# mbed_programmer_1.net
KiCad netlist of a schematic drawn in Altium Designer
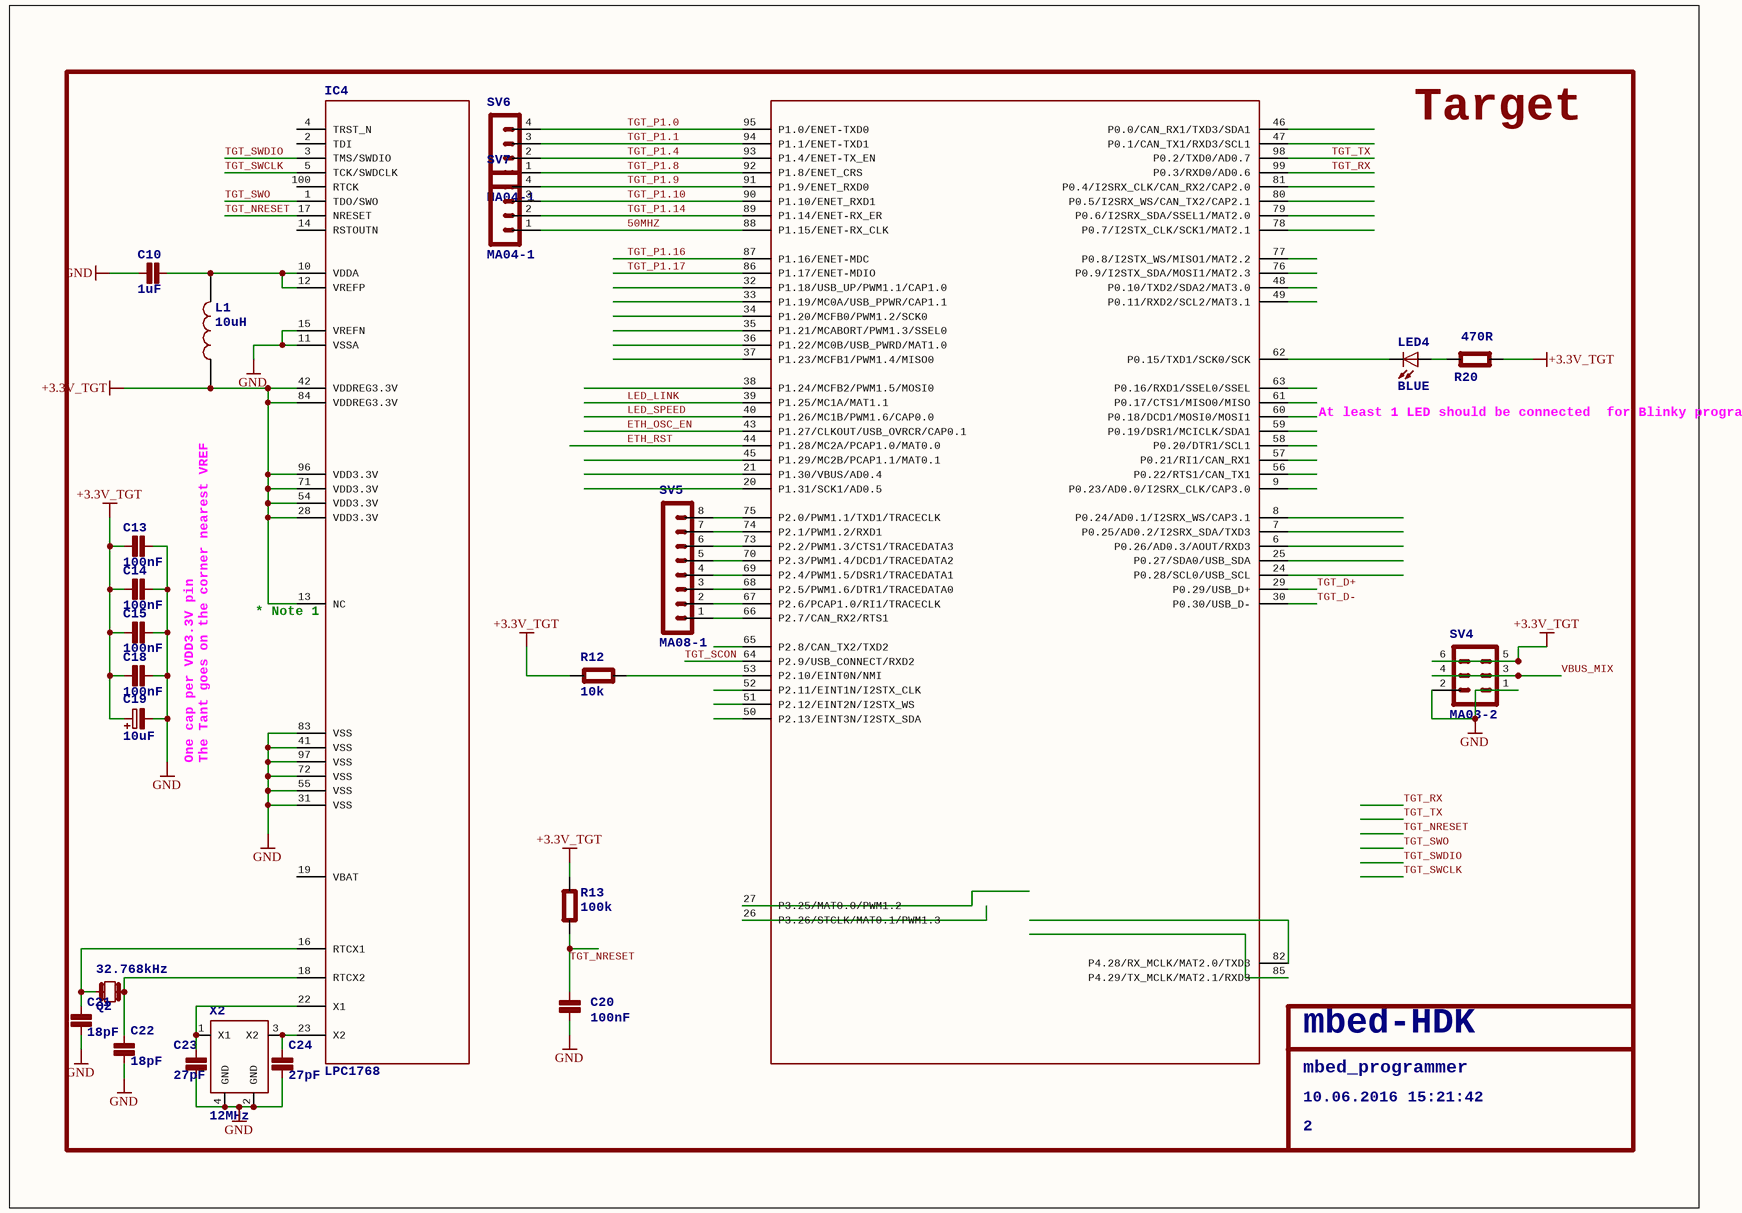
[diagram p0: mbed_programmer_1.SchDoc]

(export (version "E")
  (design (tool "Eeschema 10.0.6"))
  (components
    (comp (ref "C10") (value "1uF") (footprint "0603") (libsource (lib "") (part "C0603_2")))
    (comp (ref "C13") (value "100nF") (footprint "0603") (libsource (lib "mbed-HDK") (part "C0603")))
    (comp (ref "C14") (value "100nF") (footprint "0603") (libsource (lib "mbed-HDK") (part "C0603")))
    (comp (ref "C15") (value "100nF") (footprint "0603") (libsource (lib "mbed-HDK") (part "C0603")))
    (comp (ref "C18") (value "100nF") (footprint "0603") (libsource (lib "mbed-HDK") (part "C0603")))
    (comp (ref "C19") (value "10uF") (footprint "CASE-B") (libsource (lib "mbed-HDK") (part "C-POLB")))
    (comp (ref "C20") (value "100nF") (footprint "0603") (libsource (lib "") (part "C0603_1")))
    (comp (ref "C21") (value "18pF") (footprint "0603") (libsource (lib "") (part "C0603_1")))
    (comp (ref "C22") (value "18pF") (footprint "0603") (libsource (lib "") (part "C0603_1")))
    (comp (ref "C23") (value "27pF") (footprint "0603") (libsource (lib "") (part "C0603_1")))
    (comp (ref "C24") (value "27pF") (footprint "0603") (libsource (lib "") (part "C0603_1")))
    (comp (ref "IC4") (value "LPC1768") (footprint "LQFP100") (libsource (lib "mbed-HDK") (part "LPC1768")))
    (comp (ref "L1") (value "10uH") (footprint "0603") (libsource (lib "mbed-HDK") (part "L")))
    (comp (ref "LED4")
      (value "BLUE")
      (footprint "CHIPLED_0603")
      (libsource (lib "mbed-HDK") (part "LED0603"))
    )
    (comp (ref "Q2") (value "32.768kHz") (footprint "FC135") (libsource (lib "mbed-HDK") (part "Q_FC135")))
    (comp (ref "R12") (value "10k") (footprint "0603") (libsource (lib "mbed-HDK") (part "R0603")))
    (comp (ref "R13") (value "100k") (footprint "0603") (libsource (lib "mbed-HDK") (part "R0603")))
    (comp (ref "R20") (value "470R") (footprint "0603") (libsource (lib "mbed-HDK") (part "R0603")))
    (comp (ref "SV4")
      (value "MA03-2")
      (footprint "MA03-2")
      (description "PIN HEADER")
      (libsource (lib "con-lstb") (part "MA03-2"))
    )
    (comp (ref "SV5")
      (value "MA08-1")
      (footprint "MA08-1")
      (description "PIN HEADER")
      (libsource (lib "con-lstb") (part "MA08-1"))
    )
    (comp (ref "SV6")
      (value "MA04-1")
      (footprint "MA04-1")
      (description "PIN HEADER")
      (libsource (lib "con-lstb") (part "MA04-1"))
    )
    (comp (ref "SV7")
      (value "MA04-1")
      (footprint "MA04-1")
      (description "PIN HEADER")
      (libsource (lib "con-lstb") (part "MA04-1"))
    )
    (comp (ref "X2")
      (value "12MHz")
      (footprint "OSC_CMD_32_25")
      (libsource (lib "crystals_oscillators") (part "ABM8"))
    )
  )
  (nets
    (net (code "1") (name "+3.3V_TGT") (class "Default")
      (node (ref "C13") (pin "1") (pinfunction "P$1_1") (pintype "passive"))
      (node (ref "C14") (pin "1") (pinfunction "P$1_1") (pintype "passive"))
      (node (ref "C15") (pin "1") (pinfunction "P$1_1") (pintype "passive"))
      (node (ref "C18") (pin "1") (pinfunction "P$1_1") (pintype "passive"))
      (node (ref "C19") (pin "1") (pinfunction "1_1") (pintype "passive"))
      (node (ref "IC4") (pin "13") (pinfunction "NC_13") (pintype "passive"))
      (node (ref "IC4") (pin "28") (pinfunction "VDD3.3V_28") (pintype "passive"))
      (node (ref "IC4") (pin "42") (pinfunction "VDDREG3.3V_42") (pintype "passive"))
      (node (ref "IC4") (pin "54") (pinfunction "VDD3.3V_54") (pintype "passive"))
      (node (ref "IC4") (pin "71") (pinfunction "VDD3.3V_71") (pintype "passive"))
      (node (ref "IC4") (pin "84") (pinfunction "VDDREG3.3V_84") (pintype "passive"))
      (node (ref "IC4") (pin "96") (pinfunction "VDD3.3V_96") (pintype "passive"))
      (node (ref "L1") (pin "1") (pinfunction "P$1_1") (pintype "passive"))
      (node (ref "R12") (pin "1") (pinfunction "P$1_1") (pintype "passive"))
      (node (ref "R13") (pin "2") (pinfunction "P$2_2") (pintype "passive"))
      (node (ref "R20") (pin "1") (pinfunction "P$1_1") (pintype "passive"))
      (node (ref "SV4") (pin "5") (pinfunction "5_5") (pintype "passive"))
      (node (ref "SV4") (pin "6") (pinfunction "6_6") (pintype "passive"))
    )
    (net (code "2") (name "/50MHZ") (class "Default")
      (node (ref "IC4") (pin "88") (pinfunction "P1.15/ENET-RX_CLK_88") (pintype "passive"))
      (node (ref "SV7") (pin "1") (pinfunction "1_1") (pintype "passive"))
    )
    (net (code "3") (name "/ETH_OSC_EN") (class "Default")
      (node (ref "IC4") (pin "43") (pinfunction "P1.27/CLKOUT/USB_OVRCR/CAP0.1_43") (pintype "passive"))
    )
    (net (code "4") (name "/ETH_RST") (class "Default")
      (node (ref "IC4") (pin "44") (pinfunction "P1.28/MC2A/PCAP1.0/MAT0.0_44") (pintype "passive"))
    )
    (net (code "5") (name "/LED_LINK") (class "Default")
      (node (ref "IC4") (pin "39") (pinfunction "P1.25/MC1A/MAT1.1_39") (pintype "passive"))
    )
    (net (code "6") (name "/LED_SPEED") (class "Default")
      (node (ref "IC4") (pin "40") (pinfunction "P1.26/MC1B/PWM1.6/CAP0.0_40") (pintype "passive"))
    )
    (net (code "7") (name "/TGT_D+") (class "Default")
      (node (ref "IC4") (pin "29") (pinfunction "P0.29/USB_D+_29") (pintype "passive"))
    )
    (net (code "8") (name "/TGT_D-") (class "Default")
      (node (ref "IC4") (pin "30") (pinfunction "P0.30/USB_D-_30") (pintype "passive"))
    )
    (net (code "9") (name "/TGT_NRESET") (class "Default")
      (node (ref "C20") (pin "2") (pinfunction "P$2_2") (pintype "passive"))
      (node (ref "IC4") (pin "17") (pinfunction "NRESET_17") (pintype "passive"))
      (node (ref "R13") (pin "1") (pinfunction "P$1_1") (pintype "passive"))
    )
    (net (code "10") (name "/TGT_P1.0") (class "Default")
      (node (ref "IC4") (pin "95") (pinfunction "P1.0/ENET-TXD0_95") (pintype "passive"))
      (node (ref "SV6") (pin "4") (pinfunction "4_4") (pintype "passive"))
    )
    (net (code "11") (name "/TGT_P1.1") (class "Default")
      (node (ref "IC4") (pin "94") (pinfunction "P1.1/ENET-TXD1_94") (pintype "passive"))
      (node (ref "SV6") (pin "3") (pinfunction "3_3") (pintype "passive"))
    )
    (net (code "12") (name "/TGT_P1.4") (class "Default")
      (node (ref "IC4") (pin "93") (pinfunction "P1.4/ENET-TX_EN_93") (pintype "passive"))
      (node (ref "SV6") (pin "2") (pinfunction "2_2") (pintype "passive"))
    )
    (net (code "13") (name "/TGT_P1.8") (class "Default")
      (node (ref "IC4") (pin "92") (pinfunction "P1.8/ENET_CRS_92") (pintype "passive"))
      (node (ref "SV6") (pin "1") (pinfunction "1_1") (pintype "passive"))
    )
    (net (code "14") (name "/TGT_P1.9") (class "Default")
      (node (ref "IC4") (pin "91") (pinfunction "P1.9/ENET_RXD0_91") (pintype "passive"))
      (node (ref "SV7") (pin "4") (pinfunction "4_4") (pintype "passive"))
    )
    (net (code "15") (name "/TGT_P1.10") (class "Default")
      (node (ref "IC4") (pin "90") (pinfunction "P1.10/ENET_RXD1_90") (pintype "passive"))
      (node (ref "SV7") (pin "3") (pinfunction "3_3") (pintype "passive"))
    )
    (net (code "16") (name "/TGT_P1.14") (class "Default")
      (node (ref "IC4") (pin "89") (pinfunction "P1.14/ENET-RX_ER_89") (pintype "passive"))
      (node (ref "SV7") (pin "2") (pinfunction "2_2") (pintype "passive"))
    )
    (net (code "17") (name "/TGT_P1.16") (class "Default")
      (node (ref "IC4") (pin "87") (pinfunction "P1.16/ENET-MDC_87") (pintype "passive"))
    )
    (net (code "18") (name "/TGT_P1.17") (class "Default")
      (node (ref "IC4") (pin "86") (pinfunction "P1.17/ENET-MDIO_86") (pintype "passive"))
    )
    (net (code "19") (name "/TGT_RX") (class "Default")
      (node (ref "IC4") (pin "99") (pinfunction "P0.3/RXD0/AD0.6_99") (pintype "passive"))
    )
    (net (code "20") (name "/TGT_SCON") (class "Default")
      (node (ref "IC4") (pin "64") (pinfunction "P2.9/USB_CONNECT/RXD2_64") (pintype "passive"))
    )
    (net (code "21") (name "/TGT_SWCLK") (class "Default")
      (node (ref "IC4") (pin "5") (pinfunction "TCK/SWDCLK_5") (pintype "passive"))
    )
    (net (code "22") (name "/TGT_SWDIO") (class "Default")
      (node (ref "IC4") (pin "3") (pinfunction "TMS/SWDIO_3") (pintype "passive"))
    )
    (net (code "23") (name "/TGT_SWO") (class "Default")
      (node (ref "IC4") (pin "1") (pinfunction "TDO/SWO_1") (pintype "passive"))
    )
    (net (code "24") (name "/TGT_TX") (class "Default")
      (node (ref "IC4") (pin "98") (pinfunction "P0.2/TXD0/AD0.7_98") (pintype "passive"))
    )
    (net (code "25") (name "/VBUS_MIX") (class "Default")
      (node (ref "SV4") (pin "3") (pinfunction "3_3") (pintype "passive"))
      (node (ref "SV4") (pin "4") (pinfunction "4_4") (pintype "passive"))
    )
    (net (code "26") (name "GND") (class "Default")
      (node (ref "C10") (pin "2") (pinfunction "P$2_2") (pintype "passive"))
      (node (ref "C13") (pin "2") (pinfunction "P$2_2") (pintype "passive"))
      (node (ref "C14") (pin "2") (pinfunction "P$2_2") (pintype "passive"))
      (node (ref "C15") (pin "2") (pinfunction "P$2_2") (pintype "passive"))
      (node (ref "C18") (pin "2") (pinfunction "P$2_2") (pintype "passive"))
      (node (ref "C19") (pin "2") (pinfunction "2_2") (pintype "passive"))
      (node (ref "C20") (pin "1") (pinfunction "P$1_1") (pintype "passive"))
      (node (ref "C21") (pin "1") (pinfunction "P$1_1") (pintype "passive"))
      (node (ref "C22") (pin "1") (pinfunction "P$1_1") (pintype "passive"))
      (node (ref "C23") (pin "1") (pinfunction "P$1_1") (pintype "passive"))
      (node (ref "C24") (pin "1") (pinfunction "P$1_1") (pintype "passive"))
      (node (ref "IC4") (pin "11") (pinfunction "VSSA_11") (pintype "passive"))
      (node (ref "IC4") (pin "15") (pinfunction "VREFN_15") (pintype "passive"))
      (node (ref "IC4") (pin "31") (pinfunction "VSS_31") (pintype "passive"))
      (node (ref "IC4") (pin "41") (pinfunction "VSS_41") (pintype "passive"))
      (node (ref "IC4") (pin "55") (pinfunction "VSS_55") (pintype "passive"))
      (node (ref "IC4") (pin "72") (pinfunction "VSS_72") (pintype "passive"))
      (node (ref "IC4") (pin "83") (pinfunction "VSS_83") (pintype "passive"))
      (node (ref "IC4") (pin "97") (pinfunction "VSS_97") (pintype "passive"))
      (node (ref "SV4") (pin "1") (pinfunction "1_1") (pintype "passive"))
      (node (ref "SV4") (pin "2") (pinfunction "2_2") (pintype "passive"))
      (node (ref "X2") (pin "2") (pinfunction "GND_2") (pintype "passive"))
      (node (ref "X2") (pin "4") (pinfunction "GND_4") (pintype "passive"))
    )
    (net (code "27") (name "Net-(C10-P$1)") (class "Default")
      (node (ref "C10") (pin "1") (pinfunction "P$1_1") (pintype "passive"))
      (node (ref "IC4") (pin "10") (pinfunction "VDDA_10") (pintype "passive"))
      (node (ref "IC4") (pin "12") (pinfunction "VREFP_12") (pintype "passive"))
      (node (ref "L1") (pin "2") (pinfunction "P$2_2") (pintype "passive"))
    )
    (net (code "28") (name "Net-(C21-P$2)") (class "Default")
      (node (ref "C21") (pin "2") (pinfunction "P$2_2") (pintype "passive"))
      (node (ref "IC4") (pin "16") (pinfunction "RTCX1_16") (pintype "passive"))
      (node (ref "Q2") (pin "X2") (pinfunction "2_X2") (pintype "passive"))
    )
    (net (code "29") (name "Net-(C22-P$2)") (class "Default")
      (node (ref "C22") (pin "2") (pinfunction "P$2_2") (pintype "passive"))
      (node (ref "IC4") (pin "18") (pinfunction "RTCX2_18") (pintype "passive"))
      (node (ref "Q2") (pin "X1") (pinfunction "1_X1") (pintype "passive"))
    )
    (net (code "30") (name "Net-(C23-P$2)") (class "Default")
      (node (ref "C23") (pin "2") (pinfunction "P$2_2") (pintype "passive"))
      (node (ref "IC4") (pin "22") (pinfunction "X1_22") (pintype "passive"))
      (node (ref "X2") (pin "1") (pinfunction "X1_1") (pintype "passive"))
    )
    (net (code "31") (name "Net-(C24-P$2)") (class "Default")
      (node (ref "C24") (pin "2") (pinfunction "P$2_2") (pintype "passive"))
      (node (ref "IC4") (pin "23") (pinfunction "X2_23") (pintype "passive"))
      (node (ref "X2") (pin "3") (pinfunction "X2_3") (pintype "passive"))
    )
    (net (code "32") (name "Net-(IC4-P0.15{slash}TXD1{slash}SCK0{slash}SCK)") (class "Default")
      (node (ref "IC4") (pin "62") (pinfunction "P0.15/TXD1/SCK0/SCK_62") (pintype "passive"))
      (node (ref "LED4") (pin "C") (pinfunction "C_C") (pintype "passive"))
    )
    (net (code "33") (name "Net-(IC4-P2.0{slash}PWM1.1{slash}TXD1{slash}TRACECLK)") (class "Default")
      (node (ref "IC4") (pin "75") (pinfunction "P2.0/PWM1.1/TXD1/TRACECLK_75") (pintype "passive"))
      (node (ref "SV5") (pin "8") (pinfunction "8_8") (pintype "passive"))
    )
    (net (code "34") (name "Net-(IC4-P2.1{slash}PWM1.2{slash}RXD1)") (class "Default")
      (node (ref "IC4") (pin "74") (pinfunction "P2.1/PWM1.2/RXD1_74") (pintype "passive"))
      (node (ref "SV5") (pin "7") (pinfunction "7_7") (pintype "passive"))
    )
    (net (code "35") (name "Net-(IC4-P2.2{slash}PWM1.3{slash}CTS1{slash}TRACEDATA3)") (class "Default")
      (node (ref "IC4") (pin "73") (pinfunction "P2.2/PWM1.3/CTS1/TRACEDATA3_73") (pintype "passive"))
      (node (ref "SV5") (pin "6") (pinfunction "6_6") (pintype "passive"))
    )
    (net (code "36") (name "Net-(IC4-P2.3{slash}PWM1.4{slash}DCD1{slash}TRACEDATA2)") (class "Default")
      (node (ref "IC4") (pin "70") (pinfunction "P2.3/PWM1.4/DCD1/TRACEDATA2_70") (pintype "passive"))
      (node (ref "SV5") (pin "5") (pinfunction "5_5") (pintype "passive"))
    )
    (net (code "37") (name "Net-(IC4-P2.4{slash}PWM1.5{slash}DSR1{slash}TRACEDATA1)") (class "Default")
      (node (ref "IC4") (pin "69") (pinfunction "P2.4/PWM1.5/DSR1/TRACEDATA1_69") (pintype "passive"))
      (node (ref "SV5") (pin "4") (pinfunction "4_4") (pintype "passive"))
    )
    (net (code "38") (name "Net-(IC4-P2.5{slash}PWM1.6{slash}DTR1{slash}TRACEDATA0)") (class "Default")
      (node (ref "IC4") (pin "68") (pinfunction "P2.5/PWM1.6/DTR1/TRACEDATA0_68") (pintype "passive"))
      (node (ref "SV5") (pin "3") (pinfunction "3_3") (pintype "passive"))
    )
    (net (code "39") (name "Net-(IC4-P2.6{slash}PCAP1.0{slash}RI1{slash}TRACECLK)") (class "Default")
      (node (ref "IC4") (pin "67") (pinfunction "P2.6/PCAP1.0/RI1/TRACECLK_67") (pintype "passive"))
      (node (ref "SV5") (pin "2") (pinfunction "2_2") (pintype "passive"))
    )
    (net (code "40") (name "Net-(IC4-P2.7{slash}CAN_RX2{slash}RTS1)") (class "Default")
      (node (ref "IC4") (pin "66") (pinfunction "P2.7/CAN_RX2/RTS1_66") (pintype "passive"))
      (node (ref "SV5") (pin "1") (pinfunction "1_1") (pintype "passive"))
    )
    (net (code "41") (name "Net-(IC4-P2.10{slash}EINT0N{slash}NMI)") (class "Default")
      (node (ref "IC4") (pin "53") (pinfunction "P2.10/EINT0N/NMI_53") (pintype "passive"))
      (node (ref "R12") (pin "2") (pinfunction "P$2_2") (pintype "passive"))
    )
    (net (code "42") (name "Net-(R20-P$2)") (class "Default")
      (node (ref "LED4") (pin "A") (pinfunction "A_A") (pintype "passive"))
      (node (ref "R20") (pin "2") (pinfunction "P$2_2") (pintype "passive"))
    )
    (net (code "43") (name "unconnected-(IC4-P0.0{slash}CAN_RX1{slash}TXD3{slash}SDA1-Pad46)") (class "Default")
      (node (ref "IC4") (pin "46") (pinfunction "P0.0/CAN_RX1/TXD3/SDA1_46") (pintype "passive"))
    )
    (net (code "44") (name "unconnected-(IC4-P0.1{slash}CAN_TX1{slash}RXD3{slash}SCL1-Pad47)") (class "Default")
      (node (ref "IC4") (pin "47") (pinfunction "P0.1/CAN_TX1/RXD3/SCL1_47") (pintype "passive"))
    )
    (net (code "45") (name "unconnected-(IC4-P0.4{slash}I2SRX_CLK{slash}CAN_RX2{slash}CAP2.0-Pad81)") (class "Default")
      (node (ref "IC4") (pin "81") (pinfunction "P0.4/I2SRX_CLK/CAN_RX2/CAP2.0_81") (pintype "passive"))
    )
    (net (code "46") (name "unconnected-(IC4-P0.5{slash}I2SRX_WS{slash}CAN_TX2{slash}CAP2.1-Pad80)") (class "Default")
      (node (ref "IC4") (pin "80") (pinfunction "P0.5/I2SRX_WS/CAN_TX2/CAP2.1_80") (pintype "passive"))
    )
    (net (code "47") (name "unconnected-(IC4-P0.6{slash}I2SRX_SDA{slash}SSEL1{slash}MAT2.0-Pad79)") (class "Default")
      (node (ref "IC4") (pin "79") (pinfunction "P0.6/I2SRX_SDA/SSEL1/MAT2.0_79") (pintype "passive"))
    )
    (net (code "48") (name "unconnected-(IC4-P0.7{slash}I2STX_CLK{slash}SCK1{slash}MAT2.1-Pad78)") (class "Default")
      (node (ref "IC4") (pin "78") (pinfunction "P0.7/I2STX_CLK/SCK1/MAT2.1_78") (pintype "passive"))
    )
    (net (code "49") (name "unconnected-(IC4-P0.8{slash}I2STX_WS{slash}MISO1{slash}MAT2.2-Pad77)") (class "Default")
      (node (ref "IC4") (pin "77") (pinfunction "P0.8/I2STX_WS/MISO1/MAT2.2_77") (pintype "passive"))
    )
    (net (code "50") (name "unconnected-(IC4-P0.9{slash}I2STX_SDA{slash}MOSI1{slash}MAT2.3-Pad76)") (class "Default")
      (node (ref "IC4") (pin "76") (pinfunction "P0.9/I2STX_SDA/MOSI1/MAT2.3_76") (pintype "passive"))
    )
    (net (code "51") (name "unconnected-(IC4-P0.10{slash}TXD2{slash}SDA2{slash}MAT3.0-Pad48)") (class "Default")
      (node (ref "IC4") (pin "48") (pinfunction "P0.10/TXD2/SDA2/MAT3.0_48") (pintype "passive"))
    )
    (net (code "52") (name "unconnected-(IC4-P0.11{slash}RXD2{slash}SCL2{slash}MAT3.1-Pad49)") (class "Default")
      (node (ref "IC4") (pin "49") (pinfunction "P0.11/RXD2/SCL2/MAT3.1_49") (pintype "passive"))
    )
    (net (code "53") (name "unconnected-(IC4-P0.16{slash}RXD1{slash}SSEL0{slash}SSEL-Pad63)") (class "Default")
      (node (ref "IC4") (pin "63") (pinfunction "P0.16/RXD1/SSEL0/SSEL_63") (pintype "passive"))
    )
    (net (code "54") (name "unconnected-(IC4-P0.17{slash}CTS1{slash}MISO0{slash}MISO-Pad61)") (class "Default")
      (node (ref "IC4") (pin "61") (pinfunction "P0.17/CTS1/MISO0/MISO_61") (pintype "passive"))
    )
    (net (code "55") (name "unconnected-(IC4-P0.18{slash}DCD1{slash}MOSI0{slash}MOSI1-Pad60)") (class "Default")
      (node (ref "IC4") (pin "60") (pinfunction "P0.18/DCD1/MOSI0/MOSI1_60") (pintype "passive"))
    )
    (net (code "56") (name "unconnected-(IC4-P0.19{slash}DSR1{slash}MCICLK{slash}SDA1-Pad59)") (class "Default")
      (node (ref "IC4") (pin "59") (pinfunction "P0.19/DSR1/MCICLK/SDA1_59") (pintype "passive"))
    )
    (net (code "57") (name "unconnected-(IC4-P0.20{slash}DTR1{slash}SCL1-Pad58)") (class "Default")
      (node (ref "IC4") (pin "58") (pinfunction "P0.20/DTR1/SCL1_58") (pintype "passive"))
    )
    (net (code "58") (name "unconnected-(IC4-P0.21{slash}RI1{slash}CAN_RX1-Pad57)") (class "Default")
      (node (ref "IC4") (pin "57") (pinfunction "P0.21/RI1/CAN_RX1_57") (pintype "passive"))
    )
    (net (code "59") (name "unconnected-(IC4-P0.22{slash}RTS1{slash}CAN_TX1-Pad56)") (class "Default")
      (node (ref "IC4") (pin "56") (pinfunction "P0.22/RTS1/CAN_TX1_56") (pintype "passive"))
    )
    (net (code "60") (name "unconnected-(IC4-P0.23{slash}AD0.0{slash}I2SRX_CLK{slash}CAP3.0-Pad9)") (class "Default")
      (node (ref "IC4") (pin "9") (pinfunction "P0.23/AD0.0/I2SRX_CLK/CAP3.0_9") (pintype "passive"))
    )
    (net (code "61") (name "unconnected-(IC4-P0.24{slash}AD0.1{slash}I2SRX_WS{slash}CAP3.1-Pad8)") (class "Default")
      (node (ref "IC4") (pin "8") (pinfunction "P0.24/AD0.1/I2SRX_WS/CAP3.1_8") (pintype "passive"))
    )
    (net (code "62") (name "unconnected-(IC4-P0.25{slash}AD0.2{slash}I2SRX_SDA{slash}TXD3-Pad7)") (class "Default")
      (node (ref "IC4") (pin "7") (pinfunction "P0.25/AD0.2/I2SRX_SDA/TXD3_7") (pintype "passive"))
    )
    (net (code "63") (name "unconnected-(IC4-P0.26{slash}AD0.3{slash}AOUT{slash}RXD3-Pad6)") (class "Default")
      (node (ref "IC4") (pin "6") (pinfunction "P0.26/AD0.3/AOUT/RXD3_6") (pintype "passive"))
    )
    (net (code "64") (name "unconnected-(IC4-P0.27{slash}SDA0{slash}USB_SDA-Pad25)") (class "Default")
      (node (ref "IC4") (pin "25") (pinfunction "P0.27/SDA0/USB_SDA_25") (pintype "passive"))
    )
    (net (code "65") (name "unconnected-(IC4-P0.28{slash}SCL0{slash}USB_SCL-Pad24)") (class "Default")
      (node (ref "IC4") (pin "24") (pinfunction "P0.28/SCL0/USB_SCL_24") (pintype "passive"))
    )
    (net (code "66") (name "unconnected-(IC4-P1.18{slash}USB_UP{slash}PWM1.1{slash}CAP1.0-Pad32)") (class "Default")
      (node (ref "IC4") (pin "32") (pinfunction "P1.18/USB_UP/PWM1.1/CAP1.0_32") (pintype "passive"))
    )
    (net (code "67") (name "unconnected-(IC4-P1.19{slash}MC0A{slash}USB_PPWR{slash}CAP1.1-Pad33)") (class "Default")
      (node (ref "IC4") (pin "33") (pinfunction "P1.19/MC0A/USB_PPWR/CAP1.1_33") (pintype "passive"))
    )
    (net (code "68") (name "unconnected-(IC4-P1.20{slash}MCFB0{slash}PWM1.2{slash}SCK0-Pad34)") (class "Default")
      (node (ref "IC4") (pin "34") (pinfunction "P1.20/MCFB0/PWM1.2/SCK0_34") (pintype "passive"))
    )
    (net (code "69") (name "unconnected-(IC4-P1.21{slash}MCABORT{slash}PWM1.3{slash}SSEL0-Pad35)") (class "Default")
      (node (ref "IC4") (pin "35") (pinfunction "P1.21/MCABORT/PWM1.3/SSEL0_35") (pintype "passive"))
    )
    (net (code "70") (name "unconnected-(IC4-P1.22{slash}MC0B{slash}USB_PWRD{slash}MAT1.0-Pad36)") (class "Default")
      (node (ref "IC4") (pin "36") (pinfunction "P1.22/MC0B/USB_PWRD/MAT1.0_36") (pintype "passive"))
    )
    (net (code "71") (name "unconnected-(IC4-P1.23{slash}MCFB1{slash}PWM1.4{slash}MISO0-Pad37)") (class "Default")
      (node (ref "IC4") (pin "37") (pinfunction "P1.23/MCFB1/PWM1.4/MISO0_37") (pintype "passive"))
    )
    (net (code "72") (name "unconnected-(IC4-P1.24{slash}MCFB2{slash}PWM1.5{slash}MOSI0-Pad38)") (class "Default")
      (node (ref "IC4") (pin "38") (pinfunction "P1.24/MCFB2/PWM1.5/MOSI0_38") (pintype "passive"))
    )
    (net (code "73") (name "unconnected-(IC4-P1.29{slash}MC2B{slash}PCAP1.1{slash}MAT0.1-Pad45)") (class "Default")
      (node (ref "IC4") (pin "45") (pinfunction "P1.29/MC2B/PCAP1.1/MAT0.1_45") (pintype "passive"))
    )
    (net (code "74") (name "unconnected-(IC4-P1.30{slash}VBUS{slash}AD0.4-Pad21)") (class "Default")
      (node (ref "IC4") (pin "21") (pinfunction "P1.30/VBUS/AD0.4_21") (pintype "passive"))
    )
    (net (code "75") (name "unconnected-(IC4-P1.31{slash}SCK1{slash}AD0.5-Pad20)") (class "Default")
      (node (ref "IC4") (pin "20") (pinfunction "P1.31/SCK1/AD0.5_20") (pintype "passive"))
    )
    (net (code "76") (name "unconnected-(IC4-P2.8{slash}CAN_TX2{slash}TXD2-Pad65)") (class "Default")
      (node (ref "IC4") (pin "65") (pinfunction "P2.8/CAN_TX2/TXD2_65") (pintype "passive"))
    )
    (net (code "77") (name "unconnected-(IC4-P2.11{slash}EINT1N{slash}I2STX_CLK-Pad52)") (class "Default")
      (node (ref "IC4") (pin "52") (pinfunction "P2.11/EINT1N/I2STX_CLK_52") (pintype "passive"))
    )
    (net (code "78") (name "unconnected-(IC4-P2.12{slash}EINT2N{slash}I2STX_WS-Pad51)") (class "Default")
      (node (ref "IC4") (pin "51") (pinfunction "P2.12/EINT2N/I2STX_WS_51") (pintype "passive"))
    )
    (net (code "79") (name "unconnected-(IC4-P2.13{slash}EINT3N{slash}I2STX_SDA-Pad50)") (class "Default")
      (node (ref "IC4") (pin "50") (pinfunction "P2.13/EINT3N/I2STX_SDA_50") (pintype "passive"))
    )
    (net (code "80") (name "unconnected-(IC4-P3.25{slash}MAT0.0{slash}PWM1.2-Pad27)") (class "Default")
      (node (ref "IC4") (pin "27") (pinfunction "P3.25/MAT0.0/PWM1.2_27") (pintype "passive"))
    )
    (net (code "81") (name "unconnected-(IC4-P3.26{slash}STCLK{slash}MAT0.1{slash}PWM1.3-Pad26)") (class "Default")
      (node (ref "IC4") (pin "26") (pinfunction "P3.26/STCLK/MAT0.1/PWM1.3_26") (pintype "passive"))
    )
    (net (code "82") (name "unconnected-(IC4-P4.28{slash}RX_MCLK{slash}MAT2.0{slash}TXD3-Pad82)") (class "Default")
      (node (ref "IC4") (pin "82") (pinfunction "P4.28/RX_MCLK/MAT2.0/TXD3_82") (pintype "passive"))
    )
    (net (code "83") (name "unconnected-(IC4-P4.29{slash}TX_MCLK{slash}MAT2.1{slash}RXD3-Pad85)") (class "Default")
      (node (ref "IC4") (pin "85") (pinfunction "P4.29/TX_MCLK/MAT2.1/RXD3_85") (pintype "passive"))
    )
    (net (code "84") (name "unconnected-(IC4-RSTOUTN-Pad14)") (class "Default")
      (node (ref "IC4") (pin "14") (pinfunction "RSTOUTN_14") (pintype "passive"))
    )
    (net (code "85") (name "unconnected-(IC4-RTCK-Pad100)") (class "Default")
      (node (ref "IC4") (pin "100") (pinfunction "RTCK_100") (pintype "passive"))
    )
    (net (code "86") (name "unconnected-(IC4-TDI-Pad2)") (class "Default")
      (node (ref "IC4") (pin "2") (pinfunction "TDI_2") (pintype "passive"))
    )
    (net (code "87") (name "unconnected-(IC4-TRST_N-Pad4)") (class "Default")
      (node (ref "IC4") (pin "4") (pinfunction "TRST_N_4") (pintype "passive"))
    )
    (net (code "88") (name "unconnected-(IC4-VBAT-Pad19)") (class "Default")
      (node (ref "IC4") (pin "19") (pinfunction "VBAT_19") (pintype "passive"))
    )
  )
)
